# accesory.net
KiCad netlist of a schematic drawn in Altium Designer
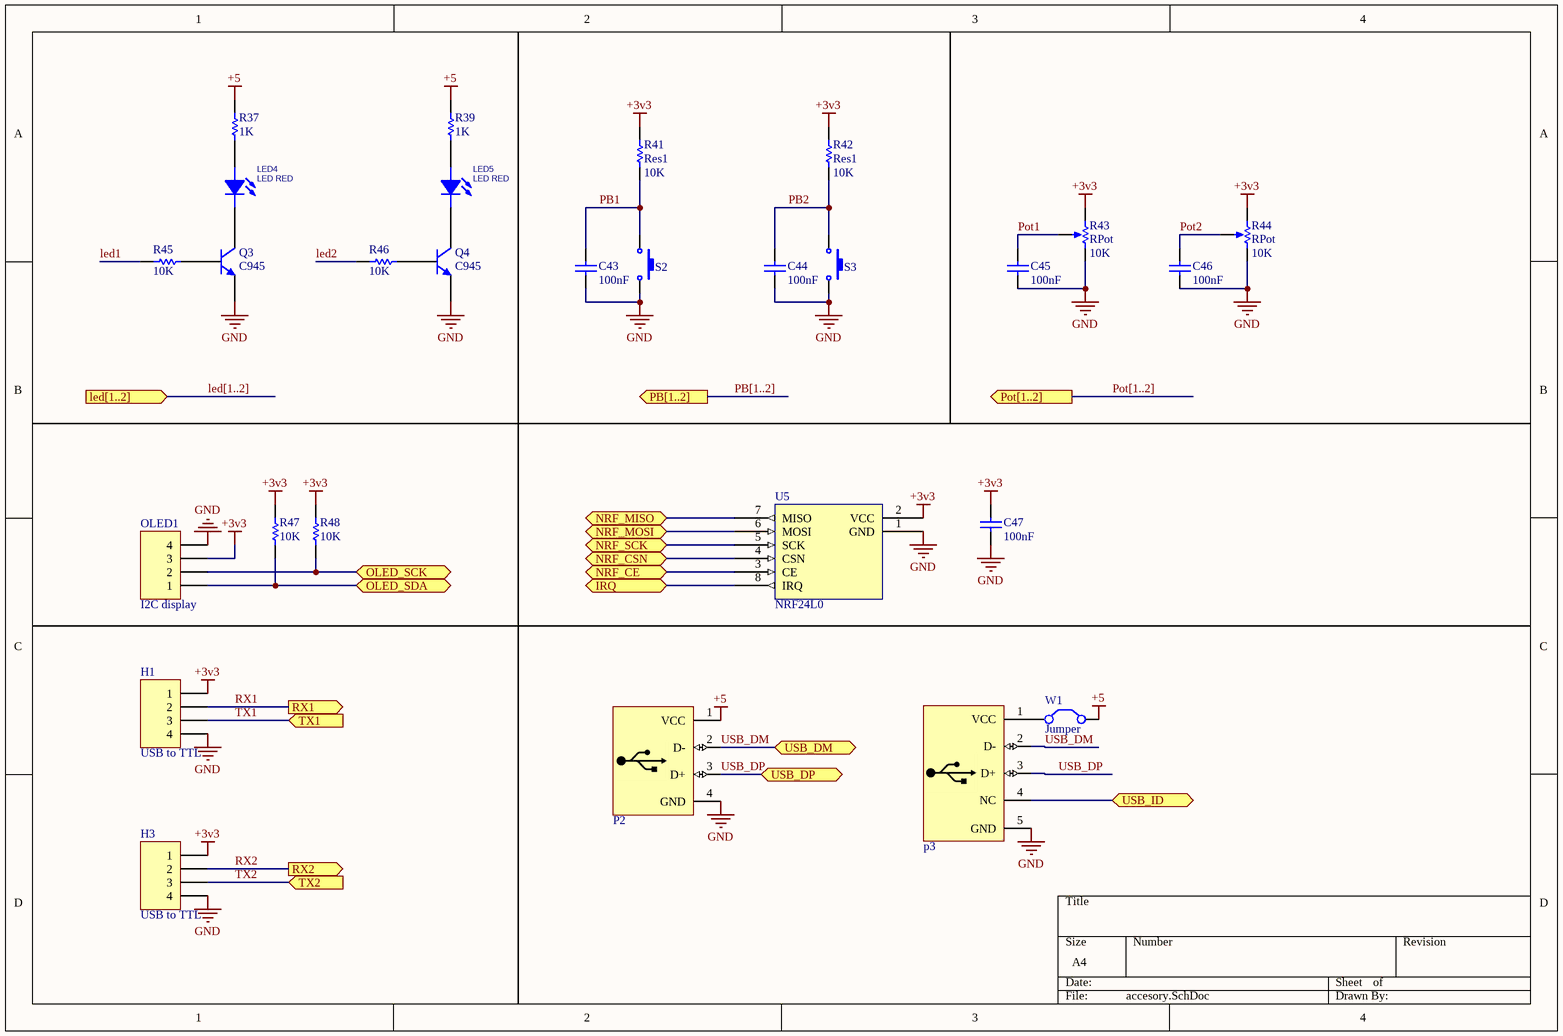
[diagram p0: accesory.SchDoc]

(export (version "E")
  (design (tool "Eeschema 10.0.6"))
  (components
    (comp (ref "C43")
      (value "100nF")
      (footprint "SMD_CAP_0805")
      (description "Capacitor")
      (fields (field (name "Comment") "Cap") (field (name "PUBLISHER") "Altium Limited"))
      (libsource (lib "Miscellaneous Devices") (part "Cap"))
    )
    (comp (ref "C44")
      (value "100nF")
      (footprint "SMD_CAP_0805")
      (description "Capacitor")
      (fields (field (name "Comment") "Cap") (field (name "PUBLISHER") "Altium Limited"))
      (libsource (lib "Miscellaneous Devices") (part "Cap"))
    )
    (comp (ref "C45")
      (value "100nF")
      (footprint "SMD_CAP_0805")
      (description "Capacitor")
      (fields (field (name "Comment") "Cap") (field (name "PUBLISHER") "Altium Limited"))
      (libsource (lib "Miscellaneous Devices") (part "Cap"))
    )
    (comp (ref "C46")
      (value "100nF")
      (footprint "SMD_CAP_0805")
      (description "Capacitor")
      (fields (field (name "Comment") "Cap") (field (name "PUBLISHER") "Altium Limited"))
      (libsource (lib "Miscellaneous Devices") (part "Cap"))
    )
    (comp (ref "C47")
      (value "100nF")
      (footprint "SMD_CAP_0805")
      (description "Capacitor")
      (fields (field (name "Comment") "Cap") (field (name "PUBLISHER") "Altium Limited"))
      (libsource (lib "Miscellaneous Devices") (part "Cap"))
    )
    (comp (ref "H1")
      (value "USB to TTL")
      (footprint "HDR1X4")
      (libsource (lib "Mine-Discreet") (part "H-1x4"))
    )
    (comp (ref "H3")
      (value "USB to TTL")
      (footprint "HDR1X4")
      (libsource (lib "Mine-Discreet") (part "H-1x4"))
    )
    (comp (ref "LED4")
      (value "LED RED")
      (footprint "led_0805")
      (description "Light Emitting Diode")
      (fields (field (name "DESIGNER") "Abbas Basereh"))
      (libsource (lib "Altium (2)") (part "LED 5MM"))
    )
    (comp (ref "LED5")
      (value "LED RED")
      (footprint "led_0805")
      (description "Light Emitting Diode")
      (fields (field (name "DESIGNER") "Abbas Basereh"))
      (libsource (lib "Altium (2)") (part "LED 5MM"))
    )
    (comp (ref "OLED1")
      (value "I2C display")
      (footprint "HDR1X4")
      (description "Header, 4-Pin")
      (fields (field (name "PUBLISHER") "Altium Limited"))
      (libsource (lib "Miscellaneous Connectors") (part "Header 4"))
    )
    (comp (ref "P2")
      (value "USB Connector")
      (footprint "USB2.5-2H4C")
      (description "USB Connector-A Type")
      (libsource (lib "Altium (2)") (part "USB A-Type"))
    )
    (comp (ref "p3")
      (value "USB Connector")
      (footprint "USB_AB_BM_SHS")
      (description "USB Connector MICRO-B Type")
      (fields (field (name "DESIGNER") "ABBAS BASEREH") (field (name "PUBLISHER") "ABBAS BASEREH"))
      (libsource (lib "Altium (2)") (part "USB MICRO"))
    )
    (comp (ref "Q3")
      (value "C945")
      (footprint "SOT23_N")
      (description "NPN Silicon Epitaxial Planar Transistor")
      (fields (field (name "PUBLISHER") "Abbas Basereh"))
      (libsource (lib "Altium (2)") (part "C945"))
    )
    (comp (ref "Q4")
      (value "C945")
      (footprint "SOT23_N")
      (description "NPN Silicon Epitaxial Planar Transistor")
      (fields (field (name "PUBLISHER") "Abbas Basereh"))
      (libsource (lib "Altium (2)") (part "C945"))
    )
    (comp (ref "R37")
      (value "1K")
      (footprint "RES 0805 (2012X06L)")
      (description "RES Axial 0.25W")
      (fields (field (name "DESIGNER") "Abbas Basereh"))
      (libsource (lib "Altium (2)") (part "RES Axial 0.25W"))
    )
    (comp (ref "R39")
      (value "1K")
      (footprint "RES 0805 (2012X06L)")
      (description "RES Axial 0.25W")
      (fields (field (name "DESIGNER") "Abbas Basereh"))
      (libsource (lib "Altium (2)") (part "RES Axial 0.25W"))
    )
    (comp (ref "R41")
      (value "Res1")
      (footprint "RES 0805 (2012X06L)")
      (description "Resistor")
      (fields (field (name "ALTIUM_VALUE") "10K") (field (name "PUBLISHER") "Altium Limited"))
      (libsource (lib "Miscellaneous Devices") (part "Res1"))
    )
    (comp (ref "R42")
      (value "Res1")
      (footprint "RES 0805 (2012X06L)")
      (description "Resistor")
      (fields (field (name "ALTIUM_VALUE") "10K") (field (name "PUBLISHER") "Altium Limited"))
      (libsource (lib "Miscellaneous Devices") (part "Res1"))
    )
    (comp (ref "R43")
      (value "RPot")
      (footprint "Multi Turn 02")
      (description "Potentiometer")
      (fields (field (name "ALTIUM_VALUE") "10K") (field (name "PUBLISHER") "Altium Limited"))
      (libsource (lib "Miscellaneous Devices") (part "RPot"))
    )
    (comp (ref "R44")
      (value "RPot")
      (footprint "Multi Turn 02")
      (description "Potentiometer")
      (fields (field (name "ALTIUM_VALUE") "10K") (field (name "PUBLISHER") "Altium Limited"))
      (libsource (lib "Miscellaneous Devices") (part "RPot"))
    )
    (comp (ref "R45")
      (value "10K")
      (footprint "RES 0805 (2012X06L)")
      (description "Resistor")
      (fields (field (name "Comment") "Res1") (field (name "PUBLISHER") "Altium Limited"))
      (libsource (lib "Miscellaneous Devices") (part "Res1"))
    )
    (comp (ref "R46")
      (value "10K")
      (footprint "RES 0805 (2012X06L)")
      (description "Resistor")
      (fields (field (name "Comment") "Res1") (field (name "PUBLISHER") "Altium Limited"))
      (libsource (lib "Miscellaneous Devices") (part "Res1"))
    )
    (comp (ref "R47")
      (value "10K")
      (footprint "RES 0805 (2012X06L)")
      (description "Resistor")
      (fields (field (name "Comment") "Res1") (field (name "PUBLISHER") "Altium Limited"))
      (libsource (lib "Miscellaneous Devices") (part "Res1"))
    )
    (comp (ref "R48")
      (value "10K")
      (footprint "RES 0805 (2012X06L)")
      (description "Resistor")
      (fields (field (name "Comment") "Res1") (field (name "PUBLISHER") "Altium Limited"))
      (libsource (lib "Miscellaneous Devices") (part "Res1"))
    )
    (comp (ref "S2")
      (value "Switch PB")
      (footprint "Switch - Push to On")
      (description "Push Button Switch")
      (libsource (lib "Altium (2)") (part "Switch PB"))
    )
    (comp (ref "S3")
      (value "Switch PB")
      (footprint "Switch - Push to On")
      (description "Push Button Switch")
      (libsource (lib "Altium (2)") (part "Switch PB"))
    )
    (comp (ref "U5")
      (value "NRF24L0")
      (footprint "RF24-MICRO STRIP")
      (libsource (lib "PA_sch") (part "NRF24"))
    )
    (comp (ref "W1")
      (value "Jumper")
      (footprint "Jumper SMD")
      (description "Jumper Wire")
      (fields (field (name "PUBLISHER") "Altium Limited"))
      (libsource (lib "Miscellaneous Devices") (part "Jumper"))
    )
  )
  (nets
    (net (code "1") (name "+3v3") (class "Default")
      (node (ref "C47") (pin "2") (pinfunction "2_2") (pintype "passive"))
      (node (ref "H1") (pin "1") (pinfunction "1_1") (pintype "passive"))
      (node (ref "H3") (pin "1") (pinfunction "1_1") (pintype "passive"))
      (node (ref "OLED1") (pin "3") (pinfunction "3_3") (pintype "passive"))
      (node (ref "R41") (pin "1") (pinfunction "1_1") (pintype "passive"))
      (node (ref "R42") (pin "1") (pinfunction "1_1") (pintype "passive"))
      (node (ref "R43") (pin "1") (pinfunction "TOP_1") (pintype "passive"))
      (node (ref "R44") (pin "1") (pinfunction "TOP_1") (pintype "passive"))
      (node (ref "R47") (pin "2") (pinfunction "2_2") (pintype "passive"))
      (node (ref "R48") (pin "2") (pinfunction "2_2") (pintype "passive"))
      (node (ref "U5") (pin "2") (pinfunction "VCC_2") (pintype "power_in"))
    )
    (net (code "2") (name "+5") (class "Default")
      (node (ref "P2") (pin "1") (pinfunction "VCC_1") (pintype "power_in"))
      (node (ref "R37") (pin "2") (pinfunction "2_2") (pintype "passive"))
      (node (ref "R39") (pin "2") (pinfunction "2_2") (pintype "passive"))
      (node (ref "W1") (pin "2") (pinfunction "C2_2") (pintype "passive"))
    )
    (net (code "3") (name "/IRQ") (class "Default")
      (node (ref "U5") (pin "8") (pinfunction "IRQ_8") (pintype "output"))
    )
    (net (code "4") (name "/NRF_CE") (class "Default")
      (node (ref "U5") (pin "3") (pinfunction "CE_3") (pintype "input"))
    )
    (net (code "5") (name "/NRF_CSN") (class "Default")
      (node (ref "U5") (pin "4") (pinfunction "CSN_4") (pintype "input"))
    )
    (net (code "6") (name "/NRF_MISO") (class "Default")
      (node (ref "U5") (pin "7") (pinfunction "MISO_7") (pintype "output"))
    )
    (net (code "7") (name "/NRF_MOSI") (class "Default")
      (node (ref "U5") (pin "6") (pinfunction "MOSI_6") (pintype "input"))
    )
    (net (code "8") (name "/NRF_SCK") (class "Default")
      (node (ref "U5") (pin "5") (pinfunction "SCK_5") (pintype "input"))
    )
    (net (code "9") (name "/OLED_SCK") (class "Default")
      (node (ref "OLED1") (pin "2") (pinfunction "2_2") (pintype "passive"))
      (node (ref "R48") (pin "1") (pinfunction "1_1") (pintype "passive"))
    )
    (net (code "10") (name "/OLED_SDA") (class "Default")
      (node (ref "OLED1") (pin "1") (pinfunction "1_1") (pintype "passive"))
      (node (ref "R47") (pin "1") (pinfunction "1_1") (pintype "passive"))
    )
    (net (code "11") (name "/PB1") (class "Default")
      (node (ref "C43") (pin "2") (pinfunction "2_2") (pintype "passive"))
      (node (ref "R41") (pin "2") (pinfunction "2_2") (pintype "passive"))
      (node (ref "S2") (pin "1") (pinfunction "1_1") (pintype "passive"))
    )
    (net (code "12") (name "/PB2") (class "Default")
      (node (ref "C44") (pin "2") (pinfunction "2_2") (pintype "passive"))
      (node (ref "R42") (pin "2") (pinfunction "2_2") (pintype "passive"))
      (node (ref "S3") (pin "1") (pinfunction "1_1") (pintype "passive"))
    )
    (net (code "14") (name "/Pot1") (class "Default")
      (node (ref "C45") (pin "2") (pinfunction "2_2") (pintype "passive"))
      (node (ref "R43") (pin "3") (pinfunction "TAP_3") (pintype "passive"))
    )
    (net (code "15") (name "/Pot2") (class "Default")
      (node (ref "C46") (pin "2") (pinfunction "2_2") (pintype "passive"))
      (node (ref "R44") (pin "3") (pinfunction "TAP_3") (pintype "passive"))
    )
    (net (code "17") (name "/RX1") (class "Default")
      (node (ref "H1") (pin "2") (pinfunction "2_2") (pintype "passive"))
    )
    (net (code "18") (name "/RX2") (class "Default")
      (node (ref "H3") (pin "2") (pinfunction "2_2") (pintype "passive"))
    )
    (net (code "19") (name "/TX1") (class "Default")
      (node (ref "H1") (pin "3") (pinfunction "3_3") (pintype "passive"))
    )
    (net (code "20") (name "/TX2") (class "Default")
      (node (ref "H3") (pin "3") (pinfunction "3_3") (pintype "passive"))
    )
    (net (code "21") (name "/USB_DM") (class "Default")
      (node (ref "P2") (pin "2") (pinfunction "D-_2") (pintype "bidirectional"))
      (node (ref "p3") (pin "2") (pinfunction "D-_2") (pintype "bidirectional"))
    )
    (net (code "22") (name "/USB_DP") (class "Default")
      (node (ref "P2") (pin "3") (pinfunction "D+_3") (pintype "bidirectional"))
      (node (ref "p3") (pin "3") (pinfunction "D+_3") (pintype "bidirectional"))
    )
    (net (code "23") (name "/USB_ID") (class "Default")
      (node (ref "p3") (pin "4") (pinfunction "NC_4") (pintype "passive"))
    )
    (net (code "24") (name "/led1") (class "Default")
      (node (ref "R45") (pin "1") (pinfunction "1_1") (pintype "passive"))
    )
    (net (code "25") (name "/led2") (class "Default")
      (node (ref "R46") (pin "1") (pinfunction "1_1") (pintype "passive"))
    )
    (net (code "27") (name "GND") (class "Default")
      (node (ref "C43") (pin "1") (pinfunction "1_1") (pintype "passive"))
      (node (ref "C44") (pin "1") (pinfunction "1_1") (pintype "passive"))
      (node (ref "C45") (pin "1") (pinfunction "1_1") (pintype "passive"))
      (node (ref "C46") (pin "1") (pinfunction "1_1") (pintype "passive"))
      (node (ref "C47") (pin "1") (pinfunction "1_1") (pintype "passive"))
      (node (ref "H1") (pin "4") (pinfunction "4_4") (pintype "passive"))
      (node (ref "H3") (pin "4") (pinfunction "4_4") (pintype "passive"))
      (node (ref "OLED1") (pin "4") (pinfunction "4_4") (pintype "passive"))
      (node (ref "P2") (pin "4") (pinfunction "GND_4") (pintype "power_in"))
      (node (ref "Q3") (pin "2") (pinfunction "E_2") (pintype "passive"))
      (node (ref "Q4") (pin "2") (pinfunction "E_2") (pintype "passive"))
      (node (ref "R43") (pin "2") (pinfunction "BOT_2") (pintype "passive"))
      (node (ref "R44") (pin "2") (pinfunction "BOT_2") (pintype "passive"))
      (node (ref "S2") (pin "2") (pinfunction "2_2") (pintype "passive"))
      (node (ref "S3") (pin "2") (pinfunction "2_2") (pintype "passive"))
      (node (ref "U5") (pin "1") (pinfunction "GND_1") (pintype "power_in"))
      (node (ref "p3") (pin "5") (pinfunction "GND_5") (pintype "power_in"))
    )
    (net (code "28") (name "Net-(LED4-ANODE)") (class "Default")
      (node (ref "LED4") (pin "1") (pinfunction "ANODE_1") (pintype "passive"))
      (node (ref "R37") (pin "1") (pinfunction "1_1") (pintype "passive"))
    )
    (net (code "29") (name "Net-(LED4-CATHODE)") (class "Default")
      (node (ref "LED4") (pin "2") (pinfunction "CATHODE_2") (pintype "passive"))
      (node (ref "Q3") (pin "3") (pinfunction "C_3") (pintype "passive"))
    )
    (net (code "30") (name "Net-(LED5-ANODE)") (class "Default")
      (node (ref "LED5") (pin "1") (pinfunction "ANODE_1") (pintype "passive"))
      (node (ref "R39") (pin "1") (pinfunction "1_1") (pintype "passive"))
    )
    (net (code "31") (name "Net-(LED5-CATHODE)") (class "Default")
      (node (ref "LED5") (pin "2") (pinfunction "CATHODE_2") (pintype "passive"))
      (node (ref "Q4") (pin "3") (pinfunction "C_3") (pintype "passive"))
    )
    (net (code "32") (name "Net-(Q3-B)") (class "Default")
      (node (ref "Q3") (pin "1") (pinfunction "B_1") (pintype "passive"))
      (node (ref "R45") (pin "2") (pinfunction "2_2") (pintype "passive"))
    )
    (net (code "33") (name "Net-(Q4-B)") (class "Default")
      (node (ref "Q4") (pin "1") (pinfunction "B_1") (pintype "passive"))
      (node (ref "R46") (pin "2") (pinfunction "2_2") (pintype "passive"))
    )
    (net (code "34") (name "Net-(W1-C1)") (class "Default")
      (node (ref "W1") (pin "1") (pinfunction "C1_1") (pintype "passive"))
      (node (ref "p3") (pin "1") (pinfunction "VCC_1") (pintype "power_in"))
    )
  )
)
